# untitled.net
KiCad netlist of a schematic drawn in EAGLE
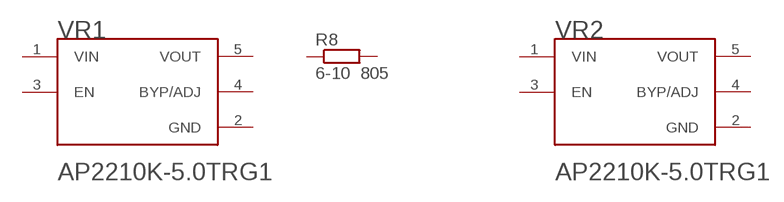
[diagram p0: schematic, sheet 1, part 1 of 2]
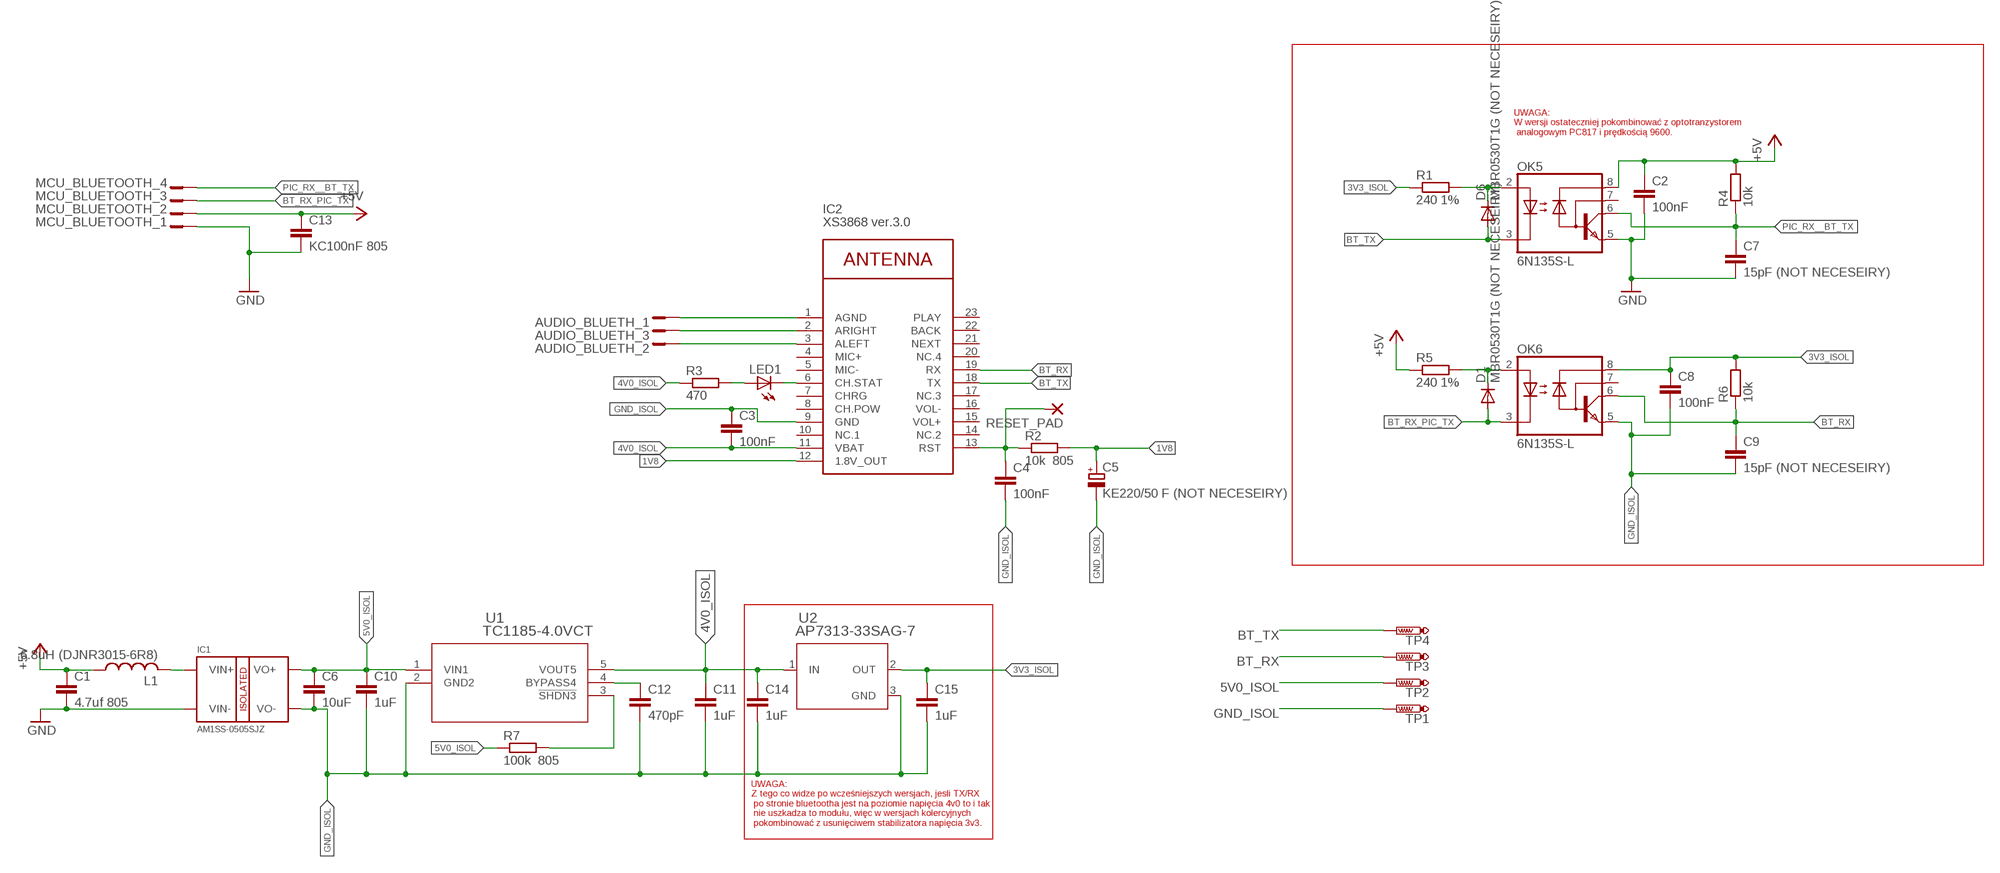
[diagram p1: schematic, sheet 1, part 2 of 2]

(export (version "E")
  (design (tool "Eeschema 10.0.6"))
  (components
    (comp (ref "AUDIO_BLUETH")
      (value "JST_3_PIN_B3B-PH-KS")
      (footprint "eagle-import:B3B-PH-KS")
      (libsource (lib "eagle-import") (part "JST_3_PIN_B3B-PH-KS"))
    )
    (comp (ref "C1")
      (value "4.7uf 805")
      (footprint "eagle-import:C0805")
      (libsource (lib "eagle-import") (part "C-EUC0805"))
    )
    (comp (ref "C2")
      (value "100nF")
      (footprint "eagle-import:C0805")
      (libsource (lib "eagle-import") (part "resistor_C-EUC0805"))
    )
    (comp (ref "C3")
      (value "100nF")
      (footprint "eagle-import:C0805")
      (libsource (lib "eagle-import") (part "resistor_C-EUC0805"))
    )
    (comp (ref "C4")
      (value "100nF")
      (footprint "eagle-import:C0805")
      (libsource (lib "eagle-import") (part "resistor_C-EUC0805"))
    )
    (comp (ref "C5")
      (value "KE220/50 F (NOT NECESEIRY)")
      (footprint "eagle-import:PANASONIC_G")
      (libsource (lib "eagle-import") (part "CPOL-EUG"))
    )
    (comp (ref "C6")
      (value "10uF")
      (footprint "eagle-import:C0805")
      (libsource (lib "eagle-import") (part "resistor_C-EUC0805"))
    )
    (comp (ref "C7")
      (value "15pF (NOT NECESEIRY)")
      (footprint "eagle-import:C0805")
      (libsource (lib "eagle-import") (part "resistor_C-EUC0805"))
    )
    (comp (ref "C8")
      (value "100nF")
      (footprint "eagle-import:C0805")
      (libsource (lib "eagle-import") (part "resistor_C-EUC0805"))
    )
    (comp (ref "C9")
      (value "15pF (NOT NECESEIRY)")
      (footprint "eagle-import:C0805")
      (libsource (lib "eagle-import") (part "resistor_C-EUC0805"))
    )
    (comp (ref "C10")
      (value "1uF")
      (footprint "eagle-import:C0805")
      (libsource (lib "eagle-import") (part "resistor_C-EUC0805"))
    )
    (comp (ref "C11")
      (value "1uF")
      (footprint "eagle-import:C0805")
      (libsource (lib "eagle-import") (part "resistor_C-EUC0805"))
    )
    (comp (ref "C12")
      (value "470pF")
      (footprint "eagle-import:C0805")
      (libsource (lib "eagle-import") (part "resistor_C-EUC0805"))
    )
    (comp (ref "C13")
      (value "KC100nF 805")
      (footprint "eagle-import:C0805")
      (libsource (lib "eagle-import") (part "C-EUC0805"))
    )
    (comp (ref "C14")
      (value "1uF")
      (footprint "eagle-import:C0805")
      (libsource (lib "eagle-import") (part "resistor_C-EUC0805"))
    )
    (comp (ref "C15")
      (value "1uF")
      (footprint "eagle-import:C0805")
      (libsource (lib "eagle-import") (part "resistor_C-EUC0805"))
    )
    (comp (ref "D1")
      (value "MBR0530T1G (NOT NECESEIRY)")
      (footprint "eagle-import:SOD123")
      (libsource (lib "eagle-import") (part "MBR0520LT"))
    )
    (comp (ref "D6")
      (value "MBR0530T1G (NOT NECESEIRY)")
      (footprint "eagle-import:SOD123")
      (libsource (lib "eagle-import") (part "MBR0520LT"))
    )
    (comp (ref "IC1")
      (value "AM1SS-0505SJZ")
      (footprint "eagle-import:SIP4")
      (libsource (lib "eagle-import") (part "AM1SS-0503S-NZ"))
    )
    (comp (ref "IC2")
      (value "XS3868 ver.3.0")
      (footprint "eagle-import:WIRELESS-BLUETOOTH-XS3868")
      (libsource (lib "eagle-import") (part "WIRELESS-BLUETOOTH-XS3868"))
    )
    (comp (ref "L1")
      (value "6.8uH (DJNR3015-6R8)")
      (footprint "eagle-import:L3230M")
      (libsource (lib "eagle-import") (part "L-USL3230M"))
    )
    (comp (ref "LED1")
      (value "LEDSMART-LED")
      (footprint "eagle-import:SMART-LED")
      (libsource (lib "eagle-import") (part "LEDSMART-LED"))
    )
    (comp (ref "MCU_BLUETOOTH")
      (value "JST_4_PIN_B4B-PH-KS")
      (footprint "eagle-import:B4B-PH-KS")
      (libsource (lib "eagle-import") (part "JST_4_PIN_B4B-PH-KS"))
    )
    (comp (ref "OK5")
      (value "6N135S-L")
      (footprint "eagle-import:DIL8-SMD")
      (libsource (lib "eagle-import") (part "6N135DIL8-SMD"))
    )
    (comp (ref "OK6")
      (value "6N135S-L")
      (footprint "eagle-import:DIL8-SMD")
      (libsource (lib "eagle-import") (part "6N135DIL8-SMD"))
    )
    (comp (ref "R1")
      (value "240 1%")
      (footprint "eagle-import:M0805")
      (libsource (lib "eagle-import") (part "R-EU_M0805"))
    )
    (comp (ref "R2")
      (value "10k 805")
      (footprint "eagle-import:M0805")
      (libsource (lib "eagle-import") (part "R-EU_M0805"))
    )
    (comp (ref "R3")
      (value "470")
      (footprint "eagle-import:M0805")
      (libsource (lib "eagle-import") (part "R-EU_M0805"))
    )
    (comp (ref "R4")
      (value "10k")
      (footprint "eagle-import:M0805")
      (libsource (lib "eagle-import") (part "R-EU_M0805"))
    )
    (comp (ref "R5")
      (value "240 1%")
      (footprint "eagle-import:M0805")
      (libsource (lib "eagle-import") (part "R-EU_M0805"))
    )
    (comp (ref "R6")
      (value "10k")
      (footprint "eagle-import:M0805")
      (libsource (lib "eagle-import") (part "R-EU_M0805"))
    )
    (comp (ref "R7")
      (value "100k 805")
      (footprint "eagle-import:M0805")
      (libsource (lib "eagle-import") (part "R-EU_M0805"))
    )
    (comp (ref "R8")
      (value "6-10 805")
      (footprint "eagle-import:M0805")
      (libsource (lib "eagle-import") (part "R-EU_M0805"))
    )
    (comp (ref "RESET_PAD")
      (value "SMD2")
      (footprint "eagle-import:SMD1,27-2,54")
      (libsource (lib "eagle-import") (part "SMD2"))
    )
    (comp (ref "TP1")
      (value "PTR1B1,27")
      (footprint "eagle-import:B1,27")
      (libsource (lib "eagle-import") (part "PTR1B1,27"))
    )
    (comp (ref "TP2")
      (value "PTR1B1,27")
      (footprint "eagle-import:B1,27")
      (libsource (lib "eagle-import") (part "PTR1B1,27"))
    )
    (comp (ref "TP3")
      (value "PTR1B1,27")
      (footprint "eagle-import:B1,27")
      (libsource (lib "eagle-import") (part "PTR1B1,27"))
    )
    (comp (ref "TP4")
      (value "PTR1B1,27")
      (footprint "eagle-import:B1,27")
      (libsource (lib "eagle-import") (part "PTR1B1,27"))
    )
    (comp (ref "U1")
      (value "TC1185-4.0VCT")
      (footprint "eagle-import:SOT-23-5_MC-M")
      (fields (field (name "MANUFACTURER_PART_NUMBER") "TC1185X.XXCT713"))
      (libsource (lib "eagle-import") (part "TC1185-X.XXCT713SOT-23-5_MC-M"))
    )
    (comp (ref "U2")
      (value "AP7313-33SAG-7")
      (footprint "eagle-import:SOT-23")
      (fields (field (name "MANUFACTURER_PART_NUMBER") "AP731333SAG7"))
      (libsource (lib "eagle-import") (part "AP7313-33SAG-7"))
    )
    (comp (ref "VR1")
      (value "DIODES_AP2210K-5.0TRG1DIODES_AP2210K-5.0TRG1_0_0")
      (footprint "eagle-import:DIODES_AP2210K-5.0TRG1_0")
      (fields
        (field (name "DIGIKEY_PART_NUMBER") "AP2210K-5.0TRG1DICT-ND")
        (field (name "MF") "Diodes")
        (field (name "MOUSER_PART_NUMBER") "621-AP2210K-5.0TRG1")
      )
      (libsource (lib "eagle-import") (part "DIODES_AP2210K-5.0TRG1DIODES_AP2210K-5.0TRG1_0_0"))
    )
    (comp (ref "VR2")
      (value "DIODES_AP2210K-5.0TRG1DIODES_AP2210K-5.0TRG1_0_0")
      (footprint "eagle-import:DIODES_AP2210K-5.0TRG1_0")
      (fields
        (field (name "DIGIKEY_PART_NUMBER") "AP2210K-5.0TRG1DICT-ND")
        (field (name "MF") "Diodes")
        (field (name "MOUSER_PART_NUMBER") "621-AP2210K-5.0TRG1")
      )
      (libsource (lib "eagle-import") (part "DIODES_AP2210K-5.0TRG1DIODES_AP2210K-5.0TRG1_0_0"))
    )
  )
  (nets
    (net (code "1") (name "+5V") (class "Default")
      (node (ref "C1") (pin "1") (pinfunction "1_1") (pintype "passive"))
      (node (ref "C13") (pin "1") (pinfunction "1_1") (pintype "passive"))
      (node (ref "C2") (pin "1") (pinfunction "1_1") (pintype "passive"))
      (node (ref "L1") (pin "1") (pinfunction "1_1") (pintype "passive"))
      (node (ref "MCU_BLUETOOTH") (pin "P$2") (pinfunction "P$1_P$2") (pintype "bidirectional"))
      (node (ref "OK5") (pin "8") (pinfunction "VCC_8") (pintype "passive"))
      (node (ref "R4") (pin "2") (pinfunction "2_2") (pintype "passive"))
      (node (ref "R5") (pin "1") (pinfunction "1_1") (pintype "passive"))
    )
    (net (code "2") (name "1V8") (class "Default")
      (node (ref "C5") (pin "+") (pinfunction "+_+") (pintype "passive"))
      (node (ref "IC2") (pin "12") (pinfunction "1.8V_OUT_12") (pintype "power_in"))
      (node (ref "R2") (pin "2") (pinfunction "2_2") (pintype "passive"))
    )
    (net (code "3") (name "3V3_ISOL") (class "Default")
      (node (ref "C15") (pin "1") (pinfunction "1_1") (pintype "passive"))
      (node (ref "C8") (pin "1") (pinfunction "1_1") (pintype "passive"))
      (node (ref "OK6") (pin "8") (pinfunction "VCC_8") (pintype "passive"))
      (node (ref "R1") (pin "1") (pinfunction "1_1") (pintype "passive"))
      (node (ref "R6") (pin "2") (pinfunction "2_2") (pintype "passive"))
      (node (ref "U2") (pin "2") (pinfunction "OUT_2") (pintype "output"))
    )
    (net (code "4") (name "4V0_ISOL") (class "Default")
      (node (ref "C11") (pin "1") (pinfunction "1_1") (pintype "passive"))
      (node (ref "C14") (pin "1") (pinfunction "1_1") (pintype "passive"))
      (node (ref "C3") (pin "2") (pinfunction "2_2") (pintype "passive"))
      (node (ref "IC2") (pin "11") (pinfunction "VBAT_11") (pintype "power_in"))
      (node (ref "R3") (pin "1") (pinfunction "1_1") (pintype "passive"))
      (node (ref "U1") (pin "5") (pinfunction "VOUT5_5") (pintype "passive"))
      (node (ref "U2") (pin "1") (pinfunction "IN_1") (pintype "input"))
    )
    (net (code "5") (name "5V0_ISOL") (class "Default")
      (node (ref "C10") (pin "1") (pinfunction "1_1") (pintype "passive"))
      (node (ref "C6") (pin "1") (pinfunction "1_1") (pintype "passive"))
      (node (ref "IC1") (pin "P$4") (pinfunction "VO+_P$4") (pintype "bidirectional"))
      (node (ref "R7") (pin "1") (pinfunction "1_1") (pintype "passive"))
      (node (ref "TP2") (pin "TP") (pinfunction "TP_TP") (pintype "input"))
      (node (ref "U1") (pin "1") (pinfunction "VIN1_1") (pintype "passive"))
    )
    (net (code "6") (name "BT_RX") (class "Default")
      (node (ref "C9") (pin "1") (pinfunction "1_1") (pintype "passive"))
      (node (ref "IC2") (pin "19") (pinfunction "RX_19") (pintype "bidirectional"))
      (node (ref "OK6") (pin "6") (pinfunction "VO_6") (pintype "passive"))
      (node (ref "R6") (pin "1") (pinfunction "1_1") (pintype "passive"))
      (node (ref "TP3") (pin "TP") (pinfunction "TP_TP") (pintype "input"))
    )
    (net (code "7") (name "BT_RX_PIC_TX") (class "Default")
      (node (ref "D1") (pin "A") (pinfunction "A_A") (pintype "passive"))
      (node (ref "MCU_BLUETOOTH") (pin "P$3") (pinfunction "P$1_P$3") (pintype "bidirectional"))
      (node (ref "OK6") (pin "3") (pinfunction "C_3") (pintype "passive"))
    )
    (net (code "8") (name "BT_TX") (class "Default")
      (node (ref "D6") (pin "A") (pinfunction "A_A") (pintype "passive"))
      (node (ref "IC2") (pin "18") (pinfunction "TX_18") (pintype "bidirectional"))
      (node (ref "OK5") (pin "3") (pinfunction "C_3") (pintype "passive"))
      (node (ref "TP4") (pin "TP") (pinfunction "TP_TP") (pintype "input"))
    )
    (net (code "9") (name "GND") (class "Default")
      (node (ref "C1") (pin "2") (pinfunction "2_2") (pintype "passive"))
      (node (ref "C13") (pin "2") (pinfunction "2_2") (pintype "passive"))
      (node (ref "C2") (pin "2") (pinfunction "2_2") (pintype "passive"))
      (node (ref "C7") (pin "2") (pinfunction "2_2") (pintype "passive"))
      (node (ref "IC1") (pin "P$1") (pinfunction "VIN-_P$1") (pintype "bidirectional"))
      (node (ref "MCU_BLUETOOTH") (pin "P$1") (pinfunction "P$1_P$1") (pintype "bidirectional"))
      (node (ref "OK5") (pin "5") (pinfunction "GND_5") (pintype "passive"))
    )
    (net (code "10") (name "GND_ISOL") (class "Default")
      (node (ref "C10") (pin "2") (pinfunction "2_2") (pintype "passive"))
      (node (ref "C11") (pin "2") (pinfunction "2_2") (pintype "passive"))
      (node (ref "C12") (pin "2") (pinfunction "2_2") (pintype "passive"))
      (node (ref "C14") (pin "2") (pinfunction "2_2") (pintype "passive"))
      (node (ref "C15") (pin "2") (pinfunction "2_2") (pintype "passive"))
      (node (ref "C3") (pin "1") (pinfunction "1_1") (pintype "passive"))
      (node (ref "C4") (pin "2") (pinfunction "2_2") (pintype "passive"))
      (node (ref "C5") (pin "-") (pinfunction "-_-") (pintype "passive"))
      (node (ref "C6") (pin "2") (pinfunction "2_2") (pintype "passive"))
      (node (ref "C8") (pin "2") (pinfunction "2_2") (pintype "passive"))
      (node (ref "C9") (pin "2") (pinfunction "2_2") (pintype "passive"))
      (node (ref "IC1") (pin "P$3") (pinfunction "VO-_P$3") (pintype "bidirectional"))
      (node (ref "IC2") (pin "9") (pinfunction "GND_9") (pintype "power_in"))
      (node (ref "OK6") (pin "5") (pinfunction "GND_5") (pintype "passive"))
      (node (ref "TP1") (pin "TP") (pinfunction "TP_TP") (pintype "input"))
      (node (ref "U1") (pin "2") (pinfunction "GND2_2") (pintype "passive"))
      (node (ref "U2") (pin "3") (pinfunction "GND_3") (pintype "power_in"))
    )
    (net (code "11") (name "Net-(AUDIO_BLUETHB-P$1)") (class "Default")
      (node (ref "AUDIO_BLUETH") (pin "P$2") (pinfunction "P$1_P$2") (pintype "bidirectional"))
      (node (ref "IC2") (pin "3") (pinfunction "ALEFT_3") (pintype "output"))
    )
    (net (code "12") (name "Net-(AUDIO_BLUETHC-P$1)") (class "Default")
      (node (ref "AUDIO_BLUETH") (pin "P$3") (pinfunction "P$1_P$3") (pintype "bidirectional"))
      (node (ref "IC2") (pin "2") (pinfunction "ARIGHT_2") (pintype "output"))
    )
    (net (code "13") (name "Net-(IC1-VIN+)") (class "Default")
      (node (ref "IC1") (pin "P$2") (pinfunction "VIN+_P$2") (pintype "bidirectional"))
      (node (ref "L1") (pin "2") (pinfunction "2_2") (pintype "passive"))
    )
    (net (code "14") (name "Net-(IC2-AGND)") (class "Default")
      (node (ref "AUDIO_BLUETH") (pin "P$1") (pinfunction "P$1_P$1") (pintype "bidirectional"))
      (node (ref "IC2") (pin "1") (pinfunction "AGND_1") (pintype "power_in"))
    )
    (net (code "15") (name "Net-(IC2-CH.STAT)") (class "Default")
      (node (ref "IC2") (pin "6") (pinfunction "CH.STAT_6") (pintype "bidirectional"))
      (node (ref "LED1") (pin "B") (pinfunction "C_B") (pintype "passive"))
    )
    (net (code "16") (name "Net-(IC2-RST)") (class "Default")
      (node (ref "C4") (pin "1") (pinfunction "1_1") (pintype "passive"))
      (node (ref "IC2") (pin "13") (pinfunction "RST_13") (pintype "power_in"))
      (node (ref "R2") (pin "1") (pinfunction "1_1") (pintype "passive"))
      (node (ref "RESET_PAD") (pin "1") (pinfunction "P_1") (pintype "passive"))
    )
    (net (code "17") (name "Net-(LED1-PadA)") (class "Default")
      (node (ref "LED1") (pin "A") (pinfunction "A_A") (pintype "passive"))
      (node (ref "R3") (pin "2") (pinfunction "2_2") (pintype "passive"))
    )
    (net (code "18") (name "Net-(OK5-A)") (class "Default")
      (node (ref "D6") (pin "C") (pinfunction "C_C") (pintype "passive"))
      (node (ref "OK5") (pin "2") (pinfunction "A_2") (pintype "passive"))
      (node (ref "R1") (pin "2") (pinfunction "2_2") (pintype "passive"))
    )
    (net (code "19") (name "Net-(OK6-A)") (class "Default")
      (node (ref "D1") (pin "C") (pinfunction "C_C") (pintype "passive"))
      (node (ref "OK6") (pin "2") (pinfunction "A_2") (pintype "passive"))
      (node (ref "R5") (pin "2") (pinfunction "2_2") (pintype "passive"))
    )
    (net (code "20") (name "Net-(U1-BYPASS4)") (class "Default")
      (node (ref "C12") (pin "1") (pinfunction "1_1") (pintype "passive"))
      (node (ref "U1") (pin "4") (pinfunction "BYPASS4_4") (pintype "passive"))
    )
    (net (code "21") (name "Net-(U1-~{SHDN3})") (class "Default")
      (node (ref "R7") (pin "2") (pinfunction "2_2") (pintype "passive"))
      (node (ref "U1") (pin "3") (pinfunction "~{SHDN3}_3") (pintype "passive"))
    )
    (net (code "22") (name "PIC_RX__BT_TX") (class "Default")
      (node (ref "C7") (pin "1") (pinfunction "1_1") (pintype "passive"))
      (node (ref "MCU_BLUETOOTH") (pin "P$4") (pinfunction "P$1_P$4") (pintype "bidirectional"))
      (node (ref "OK5") (pin "6") (pinfunction "VO_6") (pintype "passive"))
      (node (ref "R4") (pin "1") (pinfunction "1_1") (pintype "passive"))
    )
    (net (code "23") (name "unconnected-(IC2-BACK-Pad22)") (class "Default")
      (node (ref "IC2") (pin "22") (pinfunction "BACK_22") (pintype "bidirectional"))
    )
    (net (code "24") (name "unconnected-(IC2-CH.POW-Pad8)") (class "Default")
      (node (ref "IC2") (pin "8") (pinfunction "CH.POW_8") (pintype "bidirectional"))
    )
    (net (code "25") (name "unconnected-(IC2-CHRG-Pad7)") (class "Default")
      (node (ref "IC2") (pin "7") (pinfunction "CHRG_7") (pintype "bidirectional"))
    )
    (net (code "26") (name "unconnected-(IC2-MIC+-Pad4)") (class "Default")
      (node (ref "IC2") (pin "4") (pinfunction "MIC+_4") (pintype "bidirectional"))
    )
    (net (code "27") (name "unconnected-(IC2-MIC--Pad5)") (class "Default")
      (node (ref "IC2") (pin "5") (pinfunction "MIC-_5") (pintype "bidirectional"))
    )
    (net (code "28") (name "unconnected-(IC2-NC.1-Pad10)") (class "Default")
      (node (ref "IC2") (pin "10") (pinfunction "NC.1_10") (pintype "passive"))
    )
    (net (code "29") (name "unconnected-(IC2-NC.2-Pad14)") (class "Default")
      (node (ref "IC2") (pin "14") (pinfunction "NC.2_14") (pintype "passive"))
    )
    (net (code "30") (name "unconnected-(IC2-NC.3-Pad17)") (class "Default")
      (node (ref "IC2") (pin "17") (pinfunction "NC.3_17") (pintype "passive"))
    )
    (net (code "31") (name "unconnected-(IC2-NC.4-Pad20)") (class "Default")
      (node (ref "IC2") (pin "20") (pinfunction "NC.4_20") (pintype "passive"))
    )
    (net (code "32") (name "unconnected-(IC2-NEXT-Pad21)") (class "Default")
      (node (ref "IC2") (pin "21") (pinfunction "NEXT_21") (pintype "bidirectional"))
    )
    (net (code "33") (name "unconnected-(IC2-PLAY-Pad23)") (class "Default")
      (node (ref "IC2") (pin "23") (pinfunction "PLAY_23") (pintype "bidirectional"))
    )
    (net (code "34") (name "unconnected-(IC2-VOL+-Pad15)") (class "Default")
      (node (ref "IC2") (pin "15") (pinfunction "VOL+_15") (pintype "bidirectional"))
    )
    (net (code "35") (name "unconnected-(IC2-VOL--Pad16)") (class "Default")
      (node (ref "IC2") (pin "16") (pinfunction "VOL-_16") (pintype "bidirectional"))
    )
    (net (code "36") (name "unconnected-(OK5-VB-Pad7)") (class "Default")
      (node (ref "OK5") (pin "7") (pinfunction "VB_7") (pintype "passive"))
    )
    (net (code "37") (name "unconnected-(OK6-VB-Pad7)") (class "Default")
      (node (ref "OK6") (pin "7") (pinfunction "VB_7") (pintype "passive"))
    )
    (net (code "38") (name "unconnected-(R8-Pad1)") (class "Default")
      (node (ref "R8") (pin "1") (pinfunction "1_1") (pintype "passive"))
    )
    (net (code "39") (name "unconnected-(R8-Pad2)") (class "Default")
      (node (ref "R8") (pin "2") (pinfunction "2_2") (pintype "passive"))
    )
    (net (code "40") (name "unconnected-(VR1-BYP{slash}ADJ-Pad4)") (class "Default")
      (node (ref "VR1") (pin "4") (pinfunction "BYP/ADJ_4") (pintype "bidirectional"))
    )
    (net (code "41") (name "unconnected-(VR1-EN-Pad3)") (class "Default")
      (node (ref "VR1") (pin "3") (pinfunction "EN_3") (pintype "bidirectional"))
    )
    (net (code "42") (name "unconnected-(VR1-GND-Pad2)") (class "Default")
      (node (ref "VR1") (pin "2") (pinfunction "GND_2") (pintype "bidirectional"))
    )
    (net (code "43") (name "unconnected-(VR1-VIN-Pad1)") (class "Default")
      (node (ref "VR1") (pin "1") (pinfunction "VIN_1") (pintype "bidirectional"))
    )
    (net (code "44") (name "unconnected-(VR1-VOUT-Pad5)") (class "Default")
      (node (ref "VR1") (pin "5") (pinfunction "VOUT_5") (pintype "bidirectional"))
    )
    (net (code "45") (name "unconnected-(VR2-BYP{slash}ADJ-Pad4)") (class "Default")
      (node (ref "VR2") (pin "4") (pinfunction "BYP/ADJ_4") (pintype "bidirectional"))
    )
    (net (code "46") (name "unconnected-(VR2-EN-Pad3)") (class "Default")
      (node (ref "VR2") (pin "3") (pinfunction "EN_3") (pintype "bidirectional"))
    )
    (net (code "47") (name "unconnected-(VR2-GND-Pad2)") (class "Default")
      (node (ref "VR2") (pin "2") (pinfunction "GND_2") (pintype "bidirectional"))
    )
    (net (code "48") (name "unconnected-(VR2-VIN-Pad1)") (class "Default")
      (node (ref "VR2") (pin "1") (pinfunction "VIN_1") (pintype "bidirectional"))
    )
    (net (code "49") (name "unconnected-(VR2-VOUT-Pad5)") (class "Default")
      (node (ref "VR2") (pin "5") (pinfunction "VOUT_5") (pintype "bidirectional"))
    )
  )
)
